# Variometer.net
KiCad netlist of a schematic drawn in EasyEDA Pro
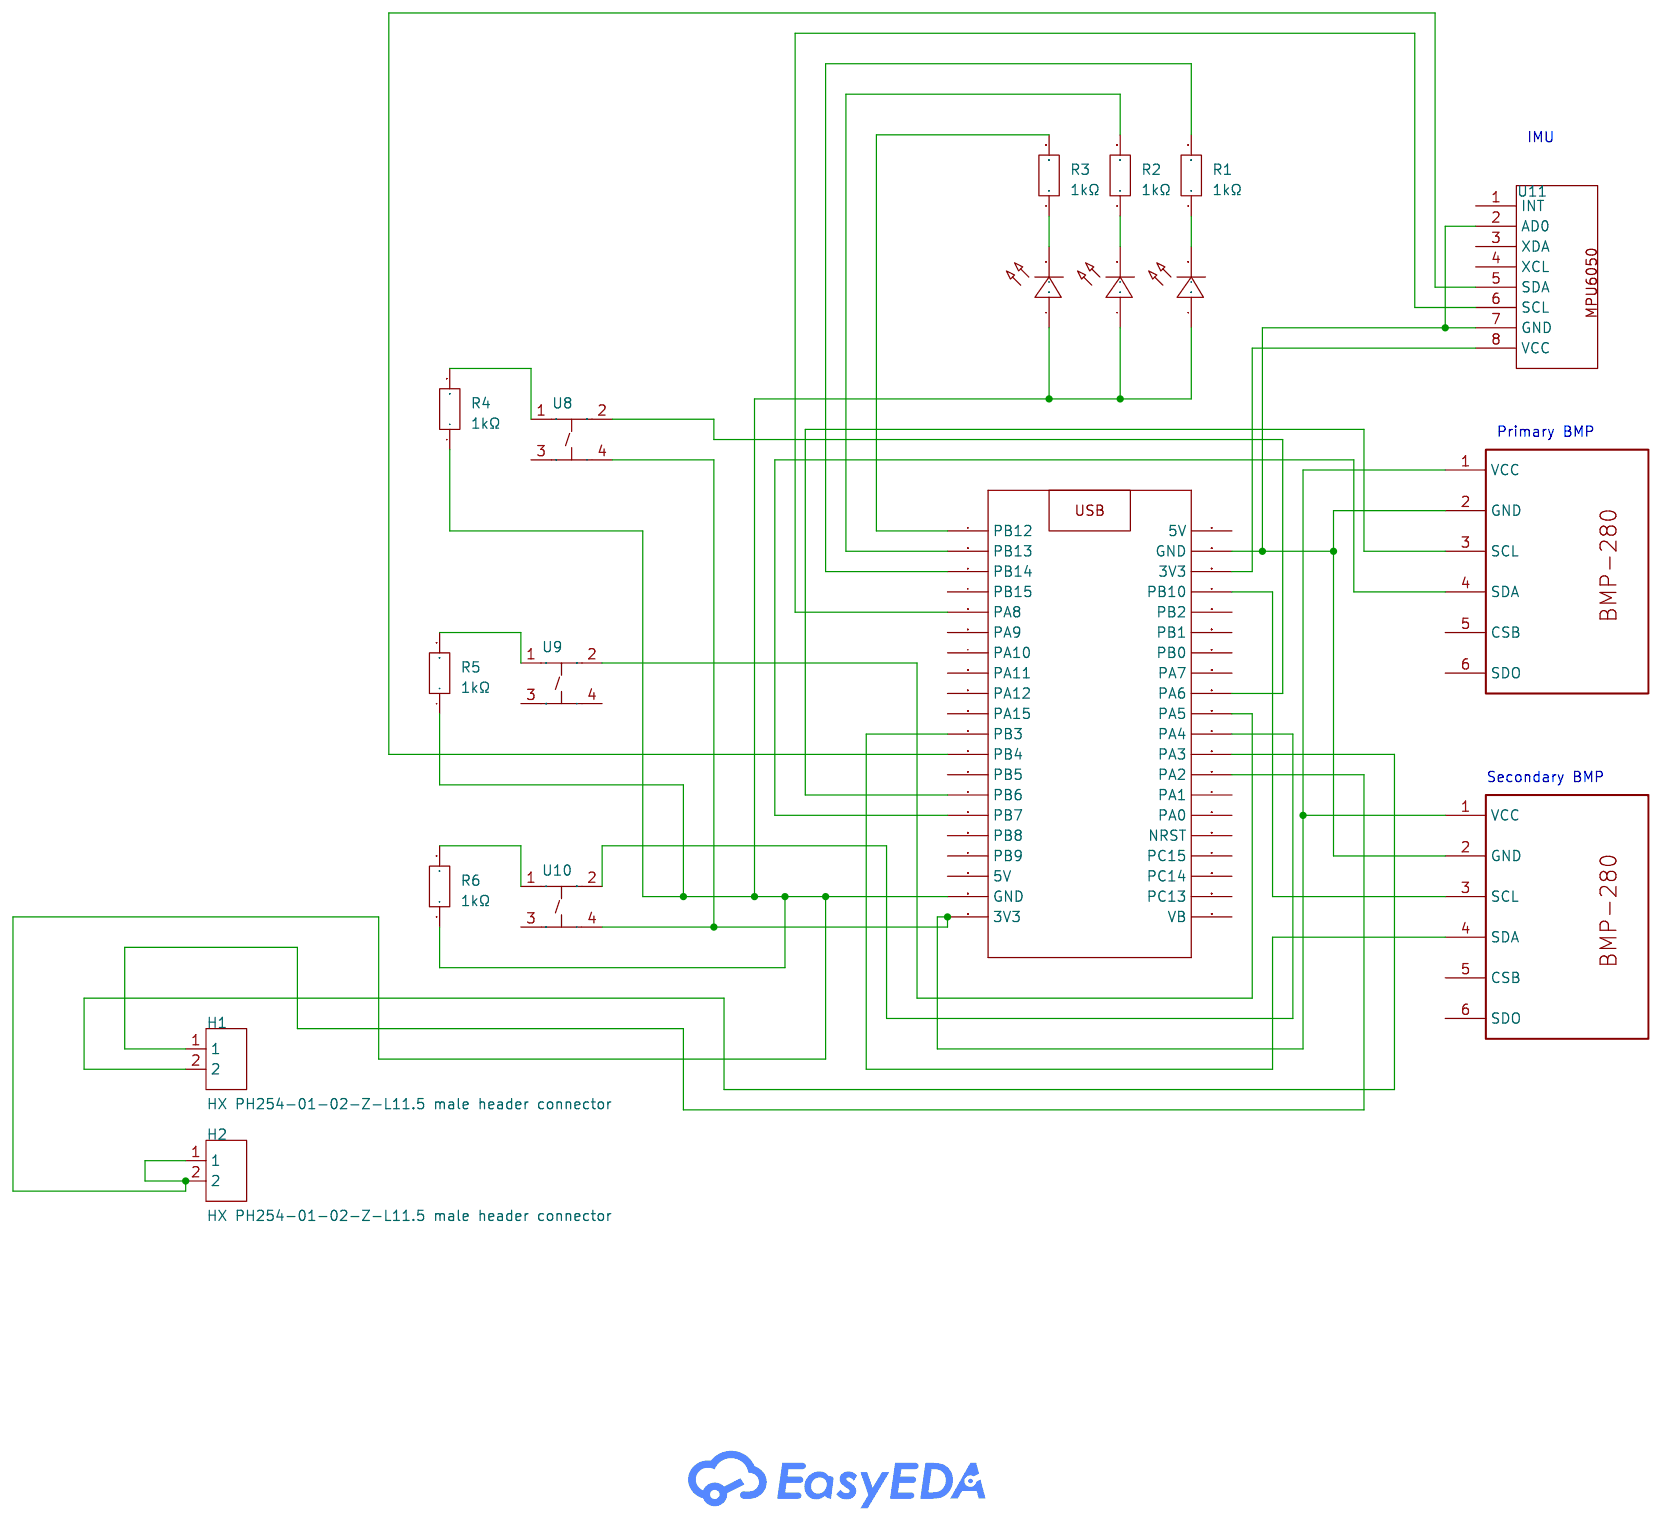
[diagram p0: schematic sheet]

(export (version "E")
  (design (tool "Eeschema 10.0.6"))
  (components
    (comp (ref "H1")
      (value "HX PH254-01-02-Z-L11.5 male header connector")
      (footprint "easyedapro:HDR-TH_2P-P2.54-V-M")
      (fields (field (name "Manufacturer") "hanxia(韩下)"))
      (libsource (lib "easyedapro") (part "HX PH254-01-02-Z-L11.5 MALE HEADER CONNECTOR"))
    )
    (comp (ref "H2")
      (value "HX PH254-01-02-Z-L11.5 male header connector")
      (footprint "easyedapro:HDR-TH_2P-P2.54-V-M")
      (fields (field (name "Manufacturer") "hanxia(韩下)"))
      (libsource (lib "easyedapro") (part "HX PH254-01-02-Z-L11.5 MALE HEADER CONNECTOR"))
    )
    (comp (ref "LED1")
      (value "~")
      (footprint "easyedapro:LED-TH_BD3.0-P2.54-FD")
      (libsource (lib "easyedapro") (part "LED_TH-R"))
    )
    (comp (ref "LED2")
      (value "~")
      (footprint "easyedapro:LED-TH_BD3.0-P2.54-FD")
      (libsource (lib "easyedapro") (part "LED_TH-R"))
    )
    (comp (ref "LED3")
      (value "~")
      (footprint "easyedapro:LED-TH_BD3.0-P2.54-FD")
      (libsource (lib "easyedapro") (part "LED_TH-R"))
    )
    (comp (ref "R1")
      (value "1kΩ")
      (footprint "easyedapro:RES-TH_BD2.7-L6.2-P10.20-D0.4")
      (fields (field (name "Manufacturer Part") "MF1/4W-1K±1%-ST52") (field (name "Manufacturer") "VO(翔胜)"))
      (libsource (lib "easyedapro") (part "MF1/4W-1K±1%-ST52"))
    )
    (comp (ref "R2")
      (value "1kΩ")
      (footprint "easyedapro:RES-TH_BD2.7-L6.2-P10.20-D0.4")
      (fields (field (name "Manufacturer Part") "MF1/4W-1K±1%-ST52") (field (name "Manufacturer") "VO(翔胜)"))
      (libsource (lib "easyedapro") (part "MF1/4W-1K±1%-ST52"))
    )
    (comp (ref "R3")
      (value "1kΩ")
      (footprint "easyedapro:RES-TH_BD2.7-L6.2-P10.20-D0.4")
      (fields (field (name "Manufacturer Part") "MF1/4W-1K±1%-ST52") (field (name "Manufacturer") "VO(翔胜)"))
      (libsource (lib "easyedapro") (part "MF1/4W-1K±1%-ST52"))
    )
    (comp (ref "R4")
      (value "1kΩ")
      (footprint "easyedapro:RES-TH_BD2.7-L6.2-P10.20-D0.4")
      (fields (field (name "Manufacturer Part") "MF1/4W-1K±1%-ST52") (field (name "Manufacturer") "VO(翔胜)"))
      (libsource (lib "easyedapro") (part "MF1/4W-1K±1%-ST52"))
    )
    (comp (ref "R5")
      (value "1kΩ")
      (footprint "easyedapro:RES-TH_BD2.7-L6.2-P10.20-D0.4")
      (fields (field (name "Manufacturer Part") "MF1/4W-1K±1%-ST52") (field (name "Manufacturer") "VO(翔胜)"))
      (libsource (lib "easyedapro") (part "MF1/4W-1K±1%-ST52"))
    )
    (comp (ref "R6")
      (value "1kΩ")
      (footprint "easyedapro:RES-TH_BD2.7-L6.2-P10.20-D0.4")
      (fields (field (name "Manufacturer Part") "MF1/4W-1K±1%-ST52") (field (name "Manufacturer") "VO(翔胜)"))
      (libsource (lib "easyedapro") (part "MF1/4W-1K±1%-ST52"))
    )
    (comp (ref "U5")
      (value "~")
      (footprint "easyedapro:PCB_BLACK_PILL_V2")
      (libsource (lib "easyedapro") (part "BLACKPILL"))
    )
    (comp (ref "U6")
      (value "BMP280")
      (footprint "easyedapro:BMP280FOOTPRINT")
      (libsource (lib "easyedapro") (part "BMP280"))
    )
    (comp (ref "U7")
      (value "BMP280")
      (footprint "easyedapro:BMP280FOOTPRINT")
      (libsource (lib "easyedapro") (part "BMP280"))
    )
    (comp (ref "U8")
      (value "YZA-072-10.0")
      (footprint "easyedapro:SW-SMD_4P-L6.0-W6.0-P4.5-LS9.0-YZA-072-10.0")
      (fields (field (name "Manufacturer") "YIZHI(逸致)"))
      (libsource (lib "easyedapro") (part "YZA-072-10.0"))
    )
    (comp (ref "U9")
      (value "YZA-072-10.0")
      (footprint "easyedapro:SW-SMD_4P-L6.0-W6.0-P4.5-LS9.0-YZA-072-10.0")
      (fields (field (name "Manufacturer") "YIZHI(逸致)"))
      (libsource (lib "easyedapro") (part "YZA-072-10.0"))
    )
    (comp (ref "U10")
      (value "YZA-072-10.0")
      (footprint "easyedapro:SW-SMD_4P-L6.0-W6.0-P4.5-LS9.0-YZA-072-10.0")
      (fields (field (name "Manufacturer") "YIZHI(逸致)"))
      (libsource (lib "easyedapro") (part "YZA-072-10.0"))
    )
    (comp (ref "U11")
      (value "~")
      (footprint "easyedapro:HDR-TH_8P-P2.54-V-F-1")
      (description "Gyro + Accelerometer")
      (libsource (lib "easyedapro") (part "MPU6050"))
    )
  )
  (nets
    (net (code "1") (name "Net-(LED1-A)") (class "Default")
      (node (ref "LED1") (pin "2") (pinfunction "A_2") (pintype "input"))
      (node (ref "R1") (pin "1") (pinfunction "1_1") (pintype "unspecified"))
    )
    (net (code "2") (name "Net-(LED1-C)") (class "Default")
      (node (ref "H2") (pin "1") (pinfunction "1_1") (pintype "unspecified"))
      (node (ref "H2") (pin "2") (pinfunction "2_2") (pintype "unspecified"))
      (node (ref "LED1") (pin "1") (pinfunction "C_1") (pintype "input"))
      (node (ref "LED2") (pin "1") (pinfunction "C_1") (pintype "input"))
      (node (ref "LED3") (pin "1") (pinfunction "C_1") (pintype "input"))
      (node (ref "R4") (pin "1") (pinfunction "1_1") (pintype "unspecified"))
      (node (ref "R5") (pin "1") (pinfunction "1_1") (pintype "unspecified"))
      (node (ref "R6") (pin "1") (pinfunction "1_1") (pintype "unspecified"))
      (node (ref "U5") (pin "19") (pinfunction "GND_19") (pintype "input"))
    )
    (net (code "3") (name "Net-(LED2-A)") (class "Default")
      (node (ref "LED2") (pin "2") (pinfunction "A_2") (pintype "input"))
      (node (ref "R2") (pin "1") (pinfunction "1_1") (pintype "unspecified"))
    )
    (net (code "4") (name "Net-(LED3-A)") (class "Default")
      (node (ref "LED3") (pin "2") (pinfunction "A_2") (pintype "input"))
      (node (ref "R3") (pin "1") (pinfunction "1_1") (pintype "unspecified"))
    )
    (net (code "5") (name "Net-(R4-Pad2)") (class "Default")
      (node (ref "R4") (pin "2") (pinfunction "2_2") (pintype "unspecified"))
      (node (ref "U8") (pin "1") (pinfunction "1_1") (pintype "unspecified"))
    )
    (net (code "6") (name "Net-(R5-Pad2)") (class "Default")
      (node (ref "R5") (pin "2") (pinfunction "2_2") (pintype "unspecified"))
      (node (ref "U9") (pin "1") (pinfunction "1_1") (pintype "unspecified"))
    )
    (net (code "7") (name "Net-(R6-Pad2)") (class "Default")
      (node (ref "R6") (pin "2") (pinfunction "2_2") (pintype "unspecified"))
      (node (ref "U10") (pin "1") (pinfunction "1_1") (pintype "unspecified"))
    )
    (net (code "8") (name "Net-(U5-PA2)") (class "Default")
      (node (ref "H1") (pin "1") (pinfunction "1_1") (pintype "unspecified"))
      (node (ref "U5") (pin "33") (pinfunction "PA2_33") (pintype "input"))
    )
    (net (code "9") (name "Net-(U5-PA3)") (class "Default")
      (node (ref "H1") (pin "2") (pinfunction "2_2") (pintype "unspecified"))
      (node (ref "U5") (pin "32") (pinfunction "PA3_32") (pintype "input"))
    )
    (net (code "10") (name "Net-(U5-PA4)") (class "Default")
      (node (ref "U10") (pin "2") (pinfunction "2_2") (pintype "unspecified"))
      (node (ref "U5") (pin "31") (pinfunction "PA4_31") (pintype "input"))
    )
    (net (code "11") (name "Net-(U5-PA5)") (class "Default")
      (node (ref "U5") (pin "30") (pinfunction "PA5_30") (pintype "input"))
      (node (ref "U9") (pin "2") (pinfunction "2_2") (pintype "unspecified"))
    )
    (net (code "12") (name "Net-(U5-PA6)") (class "Default")
      (node (ref "U5") (pin "29") (pinfunction "PA6_29") (pintype "input"))
      (node (ref "U8") (pin "2") (pinfunction "2_2") (pintype "unspecified"))
    )
    (net (code "13") (name "Net-(U5-PB3)") (class "Default")
      (node (ref "U5") (pin "11") (pinfunction "PB3_11") (pintype "input"))
      (node (ref "U7") (pin "4") (pinfunction "SDA_4") (pintype "unspecified"))
    )
    (net (code "14") (name "Net-(U5-PB6)") (class "Default")
      (node (ref "U5") (pin "14") (pinfunction "PB6_14") (pintype "input"))
      (node (ref "U6") (pin "3") (pinfunction "SCL_3") (pintype "unspecified"))
    )
    (net (code "15") (name "Net-(U5-PB7)") (class "Default")
      (node (ref "U5") (pin "15") (pinfunction "PB7_15") (pintype "input"))
      (node (ref "U6") (pin "4") (pinfunction "SDA_4") (pintype "unspecified"))
    )
    (net (code "16") (name "Net-(U5-PB10)") (class "Default")
      (node (ref "U5") (pin "24") (pinfunction "PB10_24") (pintype "input"))
      (node (ref "U7") (pin "3") (pinfunction "SCL_3") (pintype "unspecified"))
    )
    (net (code "17") (name "Net-(U5-PB12)") (class "Default")
      (node (ref "R3") (pin "2") (pinfunction "2_2") (pintype "unspecified"))
      (node (ref "U5") (pin "1") (pinfunction "PB12_1") (pintype "input"))
    )
    (net (code "18") (name "Net-(U5-PB13)") (class "Default")
      (node (ref "R2") (pin "2") (pinfunction "2_2") (pintype "unspecified"))
      (node (ref "U5") (pin "2") (pinfunction "PB13_2") (pintype "input"))
    )
    (net (code "19") (name "Net-(U5-PB14)") (class "Default")
      (node (ref "R1") (pin "2") (pinfunction "2_2") (pintype "unspecified"))
      (node (ref "U5") (pin "3") (pinfunction "PB14_3") (pintype "input"))
    )
    (net (code "20") (name "Net-(U6-VCC)") (class "Default")
      (node (ref "U10") (pin "4") (pinfunction "4_4") (pintype "unspecified"))
      (node (ref "U5") (pin "20") (pinfunction "3V3_20") (pintype "input"))
      (node (ref "U6") (pin "1") (pinfunction "VCC_1") (pintype "unspecified"))
      (node (ref "U7") (pin "1") (pinfunction "VCC_1") (pintype "unspecified"))
      (node (ref "U8") (pin "4") (pinfunction "4_4") (pintype "unspecified"))
    )
    (net (code "21") (name "Net-(U11-AD0)") (class "Default")
      (node (ref "U11") (pin "2") (pinfunction "AD0_2") (pintype "input"))
      (node (ref "U11") (pin "7") (pinfunction "GND_7") (pintype "input"))
      (node (ref "U5") (pin "22") (pinfunction "GND_22") (pintype "input"))
      (node (ref "U6") (pin "2") (pinfunction "GND_2") (pintype "unspecified"))
      (node (ref "U7") (pin "2") (pinfunction "GND_2") (pintype "unspecified"))
    )
    (net (code "22") (name "Net-(U11-SCL)") (class "Default")
      (node (ref "U11") (pin "6") (pinfunction "SCL_6") (pintype "input"))
      (node (ref "U5") (pin "5") (pinfunction "PA8_5") (pintype "input"))
    )
    (net (code "23") (name "Net-(U11-SDA)") (class "Default")
      (node (ref "U11") (pin "5") (pinfunction "SDA_5") (pintype "input"))
      (node (ref "U5") (pin "12") (pinfunction "PB4_12") (pintype "input"))
    )
    (net (code "24") (name "Net-(U11-VCC)") (class "Default")
      (node (ref "U11") (pin "8") (pinfunction "VCC_8") (pintype "input"))
      (node (ref "U5") (pin "23") (pinfunction "3V3_23") (pintype "input"))
    )
    (net (code "25") (name "unconnected-(U5-5V-Pad18)") (class "Default")
      (node (ref "U5") (pin "18") (pinfunction "5V_18") (pintype "input"))
    )
    (net (code "26") (name "unconnected-(U5-5V-Pad21)") (class "Default")
      (node (ref "U5") (pin "21") (pinfunction "5V_21") (pintype "input"))
    )
    (net (code "27") (name "unconnected-(U5-NRST-Pad36)") (class "Default")
      (node (ref "U5") (pin "36") (pinfunction "NRST_36") (pintype "input"))
    )
    (net (code "28") (name "unconnected-(U5-PA0-Pad35)") (class "Default")
      (node (ref "U5") (pin "35") (pinfunction "PA0_35") (pintype "input"))
    )
    (net (code "29") (name "unconnected-(U5-PA1-Pad34)") (class "Default")
      (node (ref "U5") (pin "34") (pinfunction "PA1_34") (pintype "input"))
    )
    (net (code "30") (name "unconnected-(U5-PA7-Pad28)") (class "Default")
      (node (ref "U5") (pin "28") (pinfunction "PA7_28") (pintype "input"))
    )
    (net (code "31") (name "unconnected-(U5-PA9-Pad6)") (class "Default")
      (node (ref "U5") (pin "6") (pinfunction "PA9_6") (pintype "input"))
    )
    (net (code "32") (name "unconnected-(U5-PA10-Pad7)") (class "Default")
      (node (ref "U5") (pin "7") (pinfunction "PA10_7") (pintype "input"))
    )
    (net (code "33") (name "unconnected-(U5-PA11-Pad8)") (class "Default")
      (node (ref "U5") (pin "8") (pinfunction "PA11_8") (pintype "input"))
    )
    (net (code "34") (name "unconnected-(U5-PA12-Pad9)") (class "Default")
      (node (ref "U5") (pin "9") (pinfunction "PA12_9") (pintype "input"))
    )
    (net (code "35") (name "unconnected-(U5-PA15-Pad10)") (class "Default")
      (node (ref "U5") (pin "10") (pinfunction "PA15_10") (pintype "input"))
    )
    (net (code "36") (name "unconnected-(U5-PB0-Pad27)") (class "Default")
      (node (ref "U5") (pin "27") (pinfunction "PB0_27") (pintype "input"))
    )
    (net (code "37") (name "unconnected-(U5-PB1-Pad26)") (class "Default")
      (node (ref "U5") (pin "26") (pinfunction "PB1_26") (pintype "input"))
    )
    (net (code "38") (name "unconnected-(U5-PB2-Pad25)") (class "Default")
      (node (ref "U5") (pin "25") (pinfunction "PB2_25") (pintype "input"))
    )
    (net (code "39") (name "unconnected-(U5-PB5-Pad13)") (class "Default")
      (node (ref "U5") (pin "13") (pinfunction "PB5_13") (pintype "input"))
    )
    (net (code "40") (name "unconnected-(U5-PB8-Pad16)") (class "Default")
      (node (ref "U5") (pin "16") (pinfunction "PB8_16") (pintype "input"))
    )
    (net (code "41") (name "unconnected-(U5-PB9-Pad17)") (class "Default")
      (node (ref "U5") (pin "17") (pinfunction "PB9_17") (pintype "input"))
    )
    (net (code "42") (name "unconnected-(U5-PB15-Pad4)") (class "Default")
      (node (ref "U5") (pin "4") (pinfunction "PB15_4") (pintype "input"))
    )
    (net (code "43") (name "unconnected-(U5-PC13-Pad39)") (class "Default")
      (node (ref "U5") (pin "39") (pinfunction "PC13_39") (pintype "input"))
    )
    (net (code "44") (name "unconnected-(U5-PC14-Pad38)") (class "Default")
      (node (ref "U5") (pin "38") (pinfunction "PC14_38") (pintype "input"))
    )
    (net (code "45") (name "unconnected-(U5-PC15-Pad37)") (class "Default")
      (node (ref "U5") (pin "37") (pinfunction "PC15_37") (pintype "input"))
    )
    (net (code "46") (name "unconnected-(U5-VB-Pad40)") (class "Default")
      (node (ref "U5") (pin "40") (pinfunction "VB_40") (pintype "input"))
    )
    (net (code "47") (name "unconnected-(U6-CSB-Pad5)") (class "Default")
      (node (ref "U6") (pin "5") (pinfunction "CSB_5") (pintype "unspecified"))
    )
    (net (code "48") (name "unconnected-(U6-SDO-Pad6)") (class "Default")
      (node (ref "U6") (pin "6") (pinfunction "SDO_6") (pintype "unspecified"))
    )
    (net (code "49") (name "unconnected-(U7-CSB-Pad5)") (class "Default")
      (node (ref "U7") (pin "5") (pinfunction "CSB_5") (pintype "unspecified"))
    )
    (net (code "50") (name "unconnected-(U7-SDO-Pad6)") (class "Default")
      (node (ref "U7") (pin "6") (pinfunction "SDO_6") (pintype "unspecified"))
    )
    (net (code "51") (name "unconnected-(U8-Pad3)") (class "Default")
      (node (ref "U8") (pin "3") (pinfunction "3_3") (pintype "unspecified"))
    )
    (net (code "52") (name "unconnected-(U9-Pad3)") (class "Default")
      (node (ref "U9") (pin "3") (pinfunction "3_3") (pintype "unspecified"))
    )
    (net (code "53") (name "unconnected-(U9-Pad4)") (class "Default")
      (node (ref "U9") (pin "4") (pinfunction "4_4") (pintype "unspecified"))
    )
    (net (code "54") (name "unconnected-(U10-Pad3)") (class "Default")
      (node (ref "U10") (pin "3") (pinfunction "3_3") (pintype "unspecified"))
    )
    (net (code "55") (name "unconnected-(U11-INT-Pad1)") (class "Default")
      (node (ref "U11") (pin "1") (pinfunction "INT_1") (pintype "input"))
    )
    (net (code "56") (name "unconnected-(U11-XCL-Pad4)") (class "Default")
      (node (ref "U11") (pin "4") (pinfunction "XCL_4") (pintype "input"))
    )
    (net (code "57") (name "unconnected-(U11-XDA-Pad3)") (class "Default")
      (node (ref "U11") (pin "3") (pinfunction "XDA_3") (pintype "input"))
    )
  )
)
